# B4_FM__Y_SOLAR_PANEL.net
KiCad netlist of a schematic drawn in EAGLE
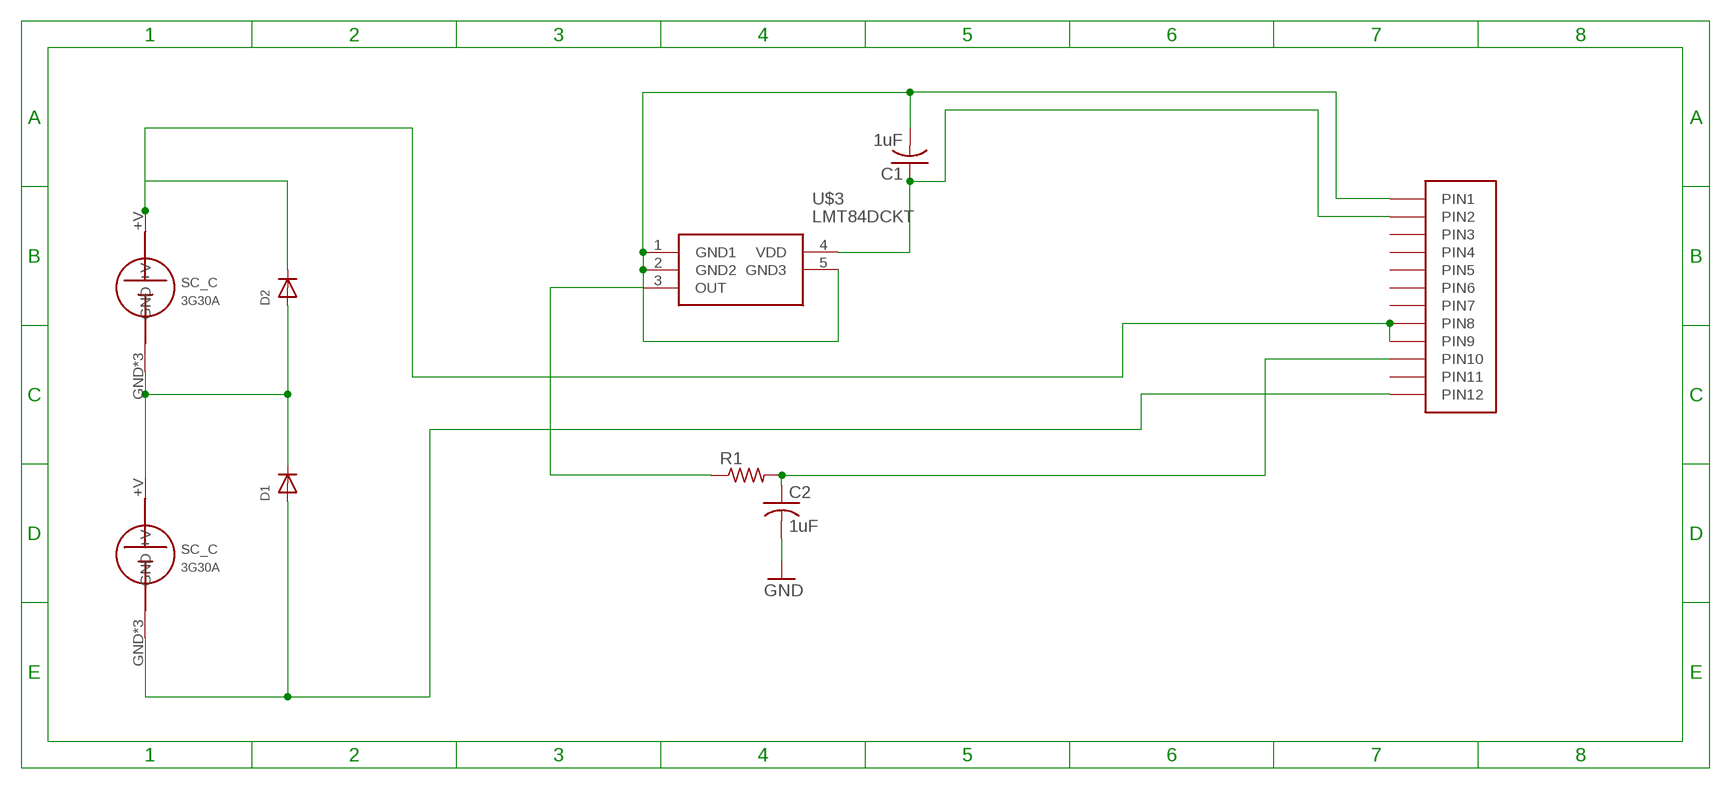
[diagram p0: schematic, sheet 1]

(export (version "E")
  (design (tool "Eeschema 10.0.6"))
  (components
    (comp (ref "C1")
      (value "1uF")
      (footprint "eagle-import:C0805")
      (libsource (lib "eagle-import") (part "C-USC0805"))
    )
    (comp (ref "C2")
      (value "1uF")
      (footprint "eagle-import:C0805")
      (libsource (lib "eagle-import") (part "C-USC0805"))
    )
    (comp (ref "D1")
      (value "DIODE_SOD-123FL")
      (footprint "eagle-import:SOD-123FL")
      (libsource (lib "eagle-import") (part "DIODE_SOD-123FL"))
    )
    (comp (ref "D2")
      (value "DIODE_SOD-123FL")
      (footprint "eagle-import:SOD-123FL")
      (libsource (lib "eagle-import") (part "DIODE_SOD-123FL"))
    )
    (comp (ref "R1")
      (value "R-US_R0402")
      (footprint "eagle-import:R0402")
      (libsource (lib "eagle-import") (part "R-US_R0402"))
    )
    (comp (ref "U$1")
      (value "HEADER12PIN")
      (footprint "eagle-import:HEADER12PIN")
      (libsource (lib "eagle-import") (part "HEADER12PIN"))
    )
    (comp (ref "U$3")
      (value "LMT84DCKT")
      (footprint "eagle-import:SOT65P210X110-5N")
      (fields (field (name "RS_PART_NUMBER") "8115860"))
      (libsource (lib "eagle-import") (part "LMT84DCKT"))
    )
    (comp (ref "U$4")
      (value "SC_C")
      (footprint "eagle-import:SC_C")
      (libsource (lib "eagle-import") (part "SC_C"))
    )
    (comp (ref "U$5")
      (value "SC_C")
      (footprint "eagle-import:SC_C")
      (libsource (lib "eagle-import") (part "SC_C"))
    )
  )
  (nets
    (net (code "1") (name "GND") (class "Default")
      (node (ref "C1") (pin "2") (pinfunction "2_2") (pintype "passive"))
      (node (ref "C2") (pin "2") (pinfunction "2_2") (pintype "passive"))
      (node (ref "D1") (pin "A") (pinfunction "A_A") (pintype "passive"))
      (node (ref "U$1") (pin "P1") (pinfunction "PIN1_P1") (pintype "bidirectional"))
      (node (ref "U$1") (pin "P12") (pinfunction "PIN12_P12") (pintype "bidirectional"))
      (node (ref "U$3") (pin "1") (pinfunction "GND1_1") (pintype "power_in"))
      (node (ref "U$3") (pin "2") (pinfunction "GND2_2") (pintype "power_in"))
      (node (ref "U$3") (pin "5") (pinfunction "GND3_5") (pintype "power_in"))
      (node (ref "U$5") (pin "GND") (pinfunction "GND_GND") (pintype "bidirectional"))
      (node (ref "U$5") (pin "GND1") (pinfunction "GND_GND1") (pintype "bidirectional"))
      (node (ref "U$5") (pin "GND2") (pinfunction "GND_GND2") (pintype "bidirectional"))
    )
    (net (code "2") (name "Net-(D1-PadC)") (class "Default")
      (node (ref "D1") (pin "C") (pinfunction "C_C") (pintype "passive"))
      (node (ref "D2") (pin "A") (pinfunction "A_A") (pintype "passive"))
      (node (ref "U$4") (pin "GND") (pinfunction "GND_GND") (pintype "bidirectional"))
      (node (ref "U$4") (pin "GND1") (pinfunction "GND_GND1") (pintype "bidirectional"))
      (node (ref "U$4") (pin "GND2") (pinfunction "GND_GND2") (pintype "bidirectional"))
      (node (ref "U$5") (pin "+V") (pinfunction "+V_+V") (pintype "bidirectional"))
    )
    (net (code "3") (name "Net-(U$1-PIN2)") (class "Default")
      (node (ref "C1") (pin "1") (pinfunction "1_1") (pintype "passive"))
      (node (ref "U$1") (pin "P2") (pinfunction "PIN2_P2") (pintype "bidirectional"))
      (node (ref "U$3") (pin "4") (pinfunction "VDD_4") (pintype "power_in"))
    )
    (net (code "4") (name "Net-(U$1-PIN8)") (class "Default")
      (node (ref "D2") (pin "C") (pinfunction "C_C") (pintype "passive"))
      (node (ref "U$1") (pin "P8") (pinfunction "PIN8_P8") (pintype "bidirectional"))
      (node (ref "U$1") (pin "P9") (pinfunction "PIN9_P9") (pintype "bidirectional"))
      (node (ref "U$4") (pin "+V") (pinfunction "+V_+V") (pintype "bidirectional"))
    )
    (net (code "5") (name "Net-(U$1-PIN10)") (class "Default")
      (node (ref "C2") (pin "1") (pinfunction "1_1") (pintype "passive"))
      (node (ref "R1") (pin "2") (pinfunction "2_2") (pintype "passive"))
      (node (ref "U$1") (pin "P10") (pinfunction "PIN10_P10") (pintype "bidirectional"))
    )
    (net (code "6") (name "Net-(U$3-OUT)") (class "Default")
      (node (ref "R1") (pin "1") (pinfunction "1_1") (pintype "passive"))
      (node (ref "U$3") (pin "3") (pinfunction "OUT_3") (pintype "output"))
    )
    (net (code "7") (name "unconnected-(U$1-PIN3-PadP3)") (class "Default")
      (node (ref "U$1") (pin "P3") (pinfunction "PIN3_P3") (pintype "bidirectional"))
    )
    (net (code "8") (name "unconnected-(U$1-PIN4-PadP4)") (class "Default")
      (node (ref "U$1") (pin "P4") (pinfunction "PIN4_P4") (pintype "bidirectional"))
    )
    (net (code "9") (name "unconnected-(U$1-PIN5-PadP5)") (class "Default")
      (node (ref "U$1") (pin "P5") (pinfunction "PIN5_P5") (pintype "bidirectional"))
    )
    (net (code "10") (name "unconnected-(U$1-PIN6-PadP6)") (class "Default")
      (node (ref "U$1") (pin "P6") (pinfunction "PIN6_P6") (pintype "bidirectional"))
    )
    (net (code "11") (name "unconnected-(U$1-PIN7-PadP7)") (class "Default")
      (node (ref "U$1") (pin "P7") (pinfunction "PIN7_P7") (pintype "bidirectional"))
    )
    (net (code "12") (name "unconnected-(U$1-PIN11-PadP11)") (class "Default")
      (node (ref "U$1") (pin "P11") (pinfunction "PIN11_P11") (pintype "bidirectional"))
    )
  )
)
